# color_sensor_node.net
KiCad netlist of a schematic drawn in EAGLE
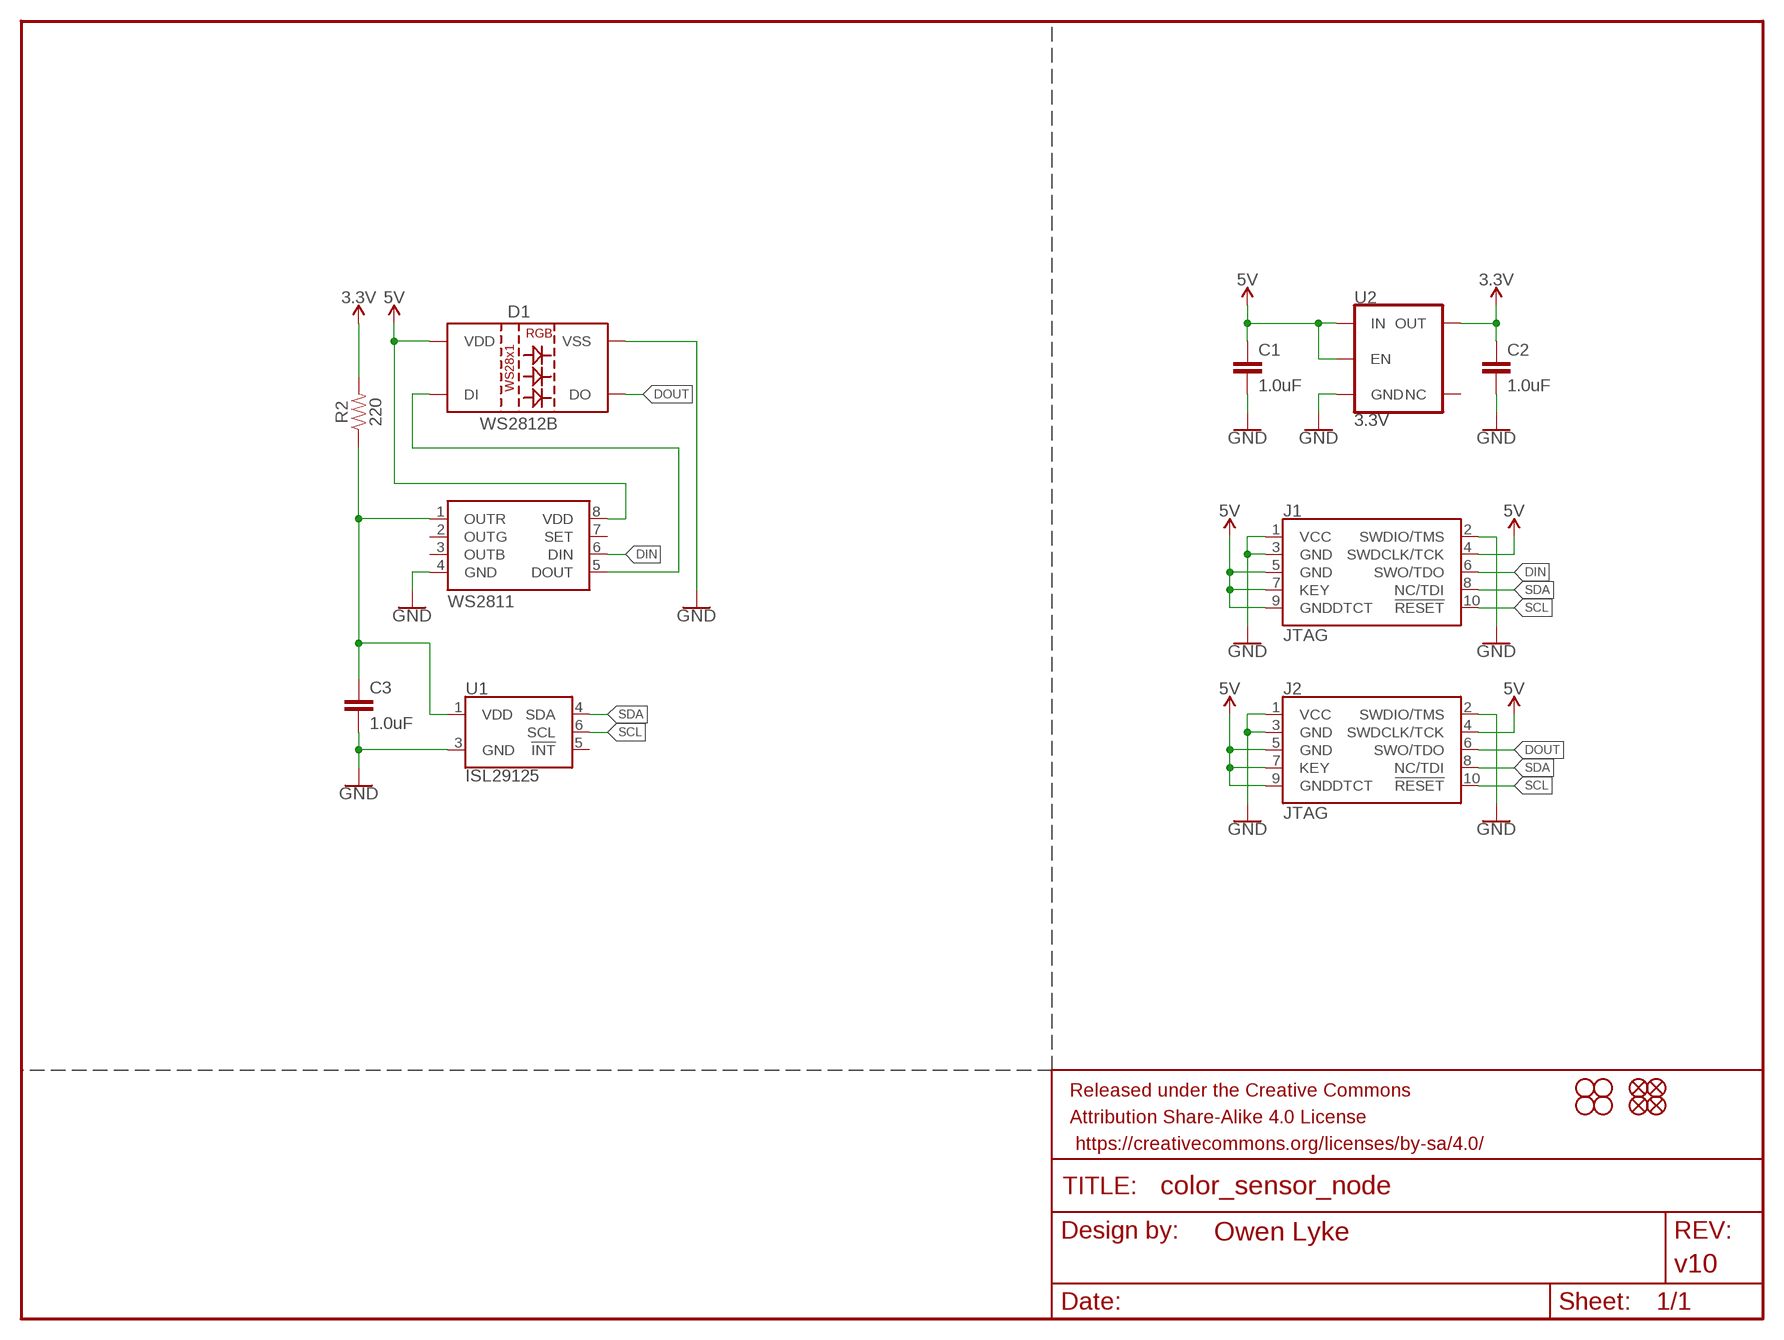
[diagram p0: schematic, sheet 1]

(export (version "E")
  (design (tool "Eeschema 10.0.6"))
  (components
    (comp (ref "C1")
      (value "1.0uF")
      (footprint "eagle-import:0603")
      (libsource (lib "eagle-import") (part "1.0UF-0603-16V-10%"))
    )
    (comp (ref "C2")
      (value "1.0uF")
      (footprint "eagle-import:0603")
      (libsource (lib "eagle-import") (part "1.0UF-0603-16V-10%"))
    )
    (comp (ref "C3")
      (value "1.0uF")
      (footprint "eagle-import:0603")
      (libsource (lib "eagle-import") (part "1.0UF-0603-16V-10%"))
    )
    (comp (ref "D1")
      (value "WS2812B")
      (footprint "eagle-import:WS2812-2020")
      (libsource (lib "eagle-import") (part "WS2812-2020"))
    )
    (comp (ref "FD1")
      (value "FIDUCIAL1X2")
      (footprint "eagle-import:FIDUCIAL-1X2")
      (libsource (lib "eagle-import") (part "FIDUCIAL1X2"))
    )
    (comp (ref "FD2")
      (value "FIDUCIAL1X2")
      (footprint "eagle-import:FIDUCIAL-1X2")
      (libsource (lib "eagle-import") (part "FIDUCIAL1X2"))
    )
    (comp (ref "FD3")
      (value "FIDUCIAL1X2")
      (footprint "eagle-import:FIDUCIAL-1X2")
      (libsource (lib "eagle-import") (part "FIDUCIAL1X2"))
    )
    (comp (ref "FD4")
      (value "FIDUCIAL1X2")
      (footprint "eagle-import:FIDUCIAL-1X2")
      (libsource (lib "eagle-import") (part "FIDUCIAL1X2"))
    )
    (comp (ref "FRAME1")
      (value "FRAME-LETTER")
      (footprint "eagle-import:CREATIVE_COMMONS")
      (fields (field (name "DESIGNER") "Owen Lyke") (field (name "REV") "v10"))
      (libsource (lib "eagle-import") (part "FRAME-LETTER"))
    )
    (comp (ref "H1")
      (value "STAND-OFF#8")
      (footprint "eagle-import:STAND-OFF-#8")
      (libsource (lib "eagle-import") (part "STAND-OFF#8"))
    )
    (comp (ref "H2")
      (value "STAND-OFF#8")
      (footprint "eagle-import:STAND-OFF-#8")
      (libsource (lib "eagle-import") (part "STAND-OFF#8"))
    )
    (comp (ref "H3")
      (value "STAND-OFF#8")
      (footprint "eagle-import:STAND-OFF-#8")
      (libsource (lib "eagle-import") (part "STAND-OFF#8"))
    )
    (comp (ref "H4")
      (value "STAND-OFF#8")
      (footprint "eagle-import:STAND-OFF-#8")
      (libsource (lib "eagle-import") (part "STAND-OFF#8"))
    )
    (comp (ref "J1")
      (value "JTAG")
      (footprint "eagle-import:2X5-SMD-1.27MM")
      (libsource (lib "eagle-import") (part "CORTEX_JTAG_DEBUG_SMD"))
    )
    (comp (ref "J2")
      (value "JTAG")
      (footprint "eagle-import:2X5-SMD-1.27MM")
      (libsource (lib "eagle-import") (part "CORTEX_JTAG_DEBUG_SMD"))
    )
    (comp (ref "R2")
      (value "220")
      (footprint "eagle-import:0603")
      (libsource (lib "eagle-import") (part "220OHM-0603-1/10W-1%"))
    )
    (comp (ref "U1")
      (value "ISL29125")
      (footprint "eagle-import:ODFN-6")
      (libsource (lib "eagle-import") (part "ISL29125"))
    )
    (comp (ref "U2")
      (value "3.3V")
      (footprint "eagle-import:SOT23-5")
      (libsource (lib "eagle-import") (part "V_REG_AP2112K-3.3V"))
    )
    (comp (ref "U3")
      (value "WS2811")
      (footprint "eagle-import:SOIC-8")
      (libsource (lib "eagle-import") (part "WS2811"))
    )
  )
  (nets
    (net (code "1") (name "3.3V") (class "Default")
      (node (ref "C2") (pin "1") (pinfunction "1_1") (pintype "passive"))
      (node (ref "R2") (pin "2") (pinfunction "2_2") (pintype "passive"))
      (node (ref "U2") (pin "5") (pinfunction "OUT_5") (pintype "passive"))
    )
    (net (code "2") (name "5V") (class "Default")
      (node (ref "C1") (pin "1") (pinfunction "1_1") (pintype "passive"))
      (node (ref "D1") (pin "4") (pinfunction "VDD_4") (pintype "bidirectional"))
      (node (ref "J1") (pin "4") (pinfunction "SWDCLK/TCK_4") (pintype "bidirectional"))
      (node (ref "J1") (pin "5") (pinfunction "GND_5") (pintype "bidirectional"))
      (node (ref "J1") (pin "7") (pinfunction "KEY_7") (pintype "bidirectional"))
      (node (ref "J1") (pin "9") (pinfunction "GNDDTCT_9") (pintype "bidirectional"))
      (node (ref "J2") (pin "4") (pinfunction "SWDCLK/TCK_4") (pintype "bidirectional"))
      (node (ref "J2") (pin "5") (pinfunction "GND_5") (pintype "bidirectional"))
      (node (ref "J2") (pin "7") (pinfunction "KEY_7") (pintype "bidirectional"))
      (node (ref "J2") (pin "9") (pinfunction "GNDDTCT_9") (pintype "bidirectional"))
      (node (ref "U2") (pin "1") (pinfunction "IN_1") (pintype "input"))
      (node (ref "U2") (pin "3") (pinfunction "EN_3") (pintype "input"))
      (node (ref "U3") (pin "8") (pinfunction "VDD_8") (pintype "bidirectional"))
    )
    (net (code "3") (name "DIN") (class "Default")
      (node (ref "J1") (pin "6") (pinfunction "SWO/TDO_6") (pintype "bidirectional"))
      (node (ref "U3") (pin "6") (pinfunction "DIN_6") (pintype "bidirectional"))
    )
    (net (code "4") (name "DOUT") (class "Default")
      (node (ref "D1") (pin "1") (pinfunction "DO_1") (pintype "bidirectional"))
      (node (ref "J2") (pin "6") (pinfunction "SWO/TDO_6") (pintype "bidirectional"))
    )
    (net (code "5") (name "GND") (class "Default")
      (node (ref "C1") (pin "2") (pinfunction "2_2") (pintype "passive"))
      (node (ref "C2") (pin "2") (pinfunction "2_2") (pintype "passive"))
      (node (ref "C3") (pin "2") (pinfunction "2_2") (pintype "passive"))
      (node (ref "D1") (pin "2") (pinfunction "VSS_2") (pintype "bidirectional"))
      (node (ref "J1") (pin "1") (pinfunction "VCC_1") (pintype "bidirectional"))
      (node (ref "J1") (pin "2") (pinfunction "SWDIO/TMS_2") (pintype "bidirectional"))
      (node (ref "J1") (pin "3") (pinfunction "GND_3") (pintype "bidirectional"))
      (node (ref "J2") (pin "1") (pinfunction "VCC_1") (pintype "bidirectional"))
      (node (ref "J2") (pin "2") (pinfunction "SWDIO/TMS_2") (pintype "bidirectional"))
      (node (ref "J2") (pin "3") (pinfunction "GND_3") (pintype "bidirectional"))
      (node (ref "U1") (pin "3") (pinfunction "GND_3") (pintype "bidirectional"))
      (node (ref "U2") (pin "2") (pinfunction "GND_2") (pintype "input"))
      (node (ref "U3") (pin "4") (pinfunction "GND_4") (pintype "bidirectional"))
    )
    (net (code "6") (name "Net-(D1-DI)") (class "Default")
      (node (ref "D1") (pin "3") (pinfunction "DI_3") (pintype "bidirectional"))
      (node (ref "U3") (pin "5") (pinfunction "DOUT_5") (pintype "bidirectional"))
    )
    (net (code "7") (name "Net-(U1-VDD)") (class "Default")
      (node (ref "C3") (pin "1") (pinfunction "1_1") (pintype "passive"))
      (node (ref "R2") (pin "1") (pinfunction "1_1") (pintype "passive"))
      (node (ref "U1") (pin "1") (pinfunction "VDD_1") (pintype "bidirectional"))
      (node (ref "U3") (pin "1") (pinfunction "OUTR_1") (pintype "bidirectional"))
    )
    (net (code "8") (name "SCL") (class "Default")
      (node (ref "J1") (pin "10") (pinfunction "~{RESET}_10") (pintype "bidirectional"))
      (node (ref "J2") (pin "10") (pinfunction "~{RESET}_10") (pintype "bidirectional"))
      (node (ref "U1") (pin "6") (pinfunction "SCL_6") (pintype "bidirectional"))
    )
    (net (code "9") (name "SDA") (class "Default")
      (node (ref "J1") (pin "8") (pinfunction "NC/TDI_8") (pintype "bidirectional"))
      (node (ref "J2") (pin "8") (pinfunction "NC/TDI_8") (pintype "bidirectional"))
      (node (ref "U1") (pin "4") (pinfunction "SDA_4") (pintype "bidirectional"))
    )
    (net (code "10") (name "unconnected-(U1-~{INT}-Pad5)") (class "Default")
      (node (ref "U1") (pin "5") (pinfunction "~{INT}_5") (pintype "bidirectional"))
    )
    (net (code "11") (name "unconnected-(U2-NC-Pad4)") (class "Default")
      (node (ref "U2") (pin "4") (pinfunction "NC_4") (pintype "no_connect"))
    )
    (net (code "12") (name "unconnected-(U3-OUTB-Pad3)") (class "Default")
      (node (ref "U3") (pin "3") (pinfunction "OUTB_3") (pintype "bidirectional"))
    )
    (net (code "13") (name "unconnected-(U3-OUTG-Pad2)") (class "Default")
      (node (ref "U3") (pin "2") (pinfunction "OUTG_2") (pintype "bidirectional"))
    )
    (net (code "14") (name "unconnected-(U3-SET-Pad7)") (class "Default")
      (node (ref "U3") (pin "7") (pinfunction "SET_7") (pintype "bidirectional"))
    )
  )
)
